# FPGA_parts.net
KiCad netlist of a schematic drawn in Altium Designer
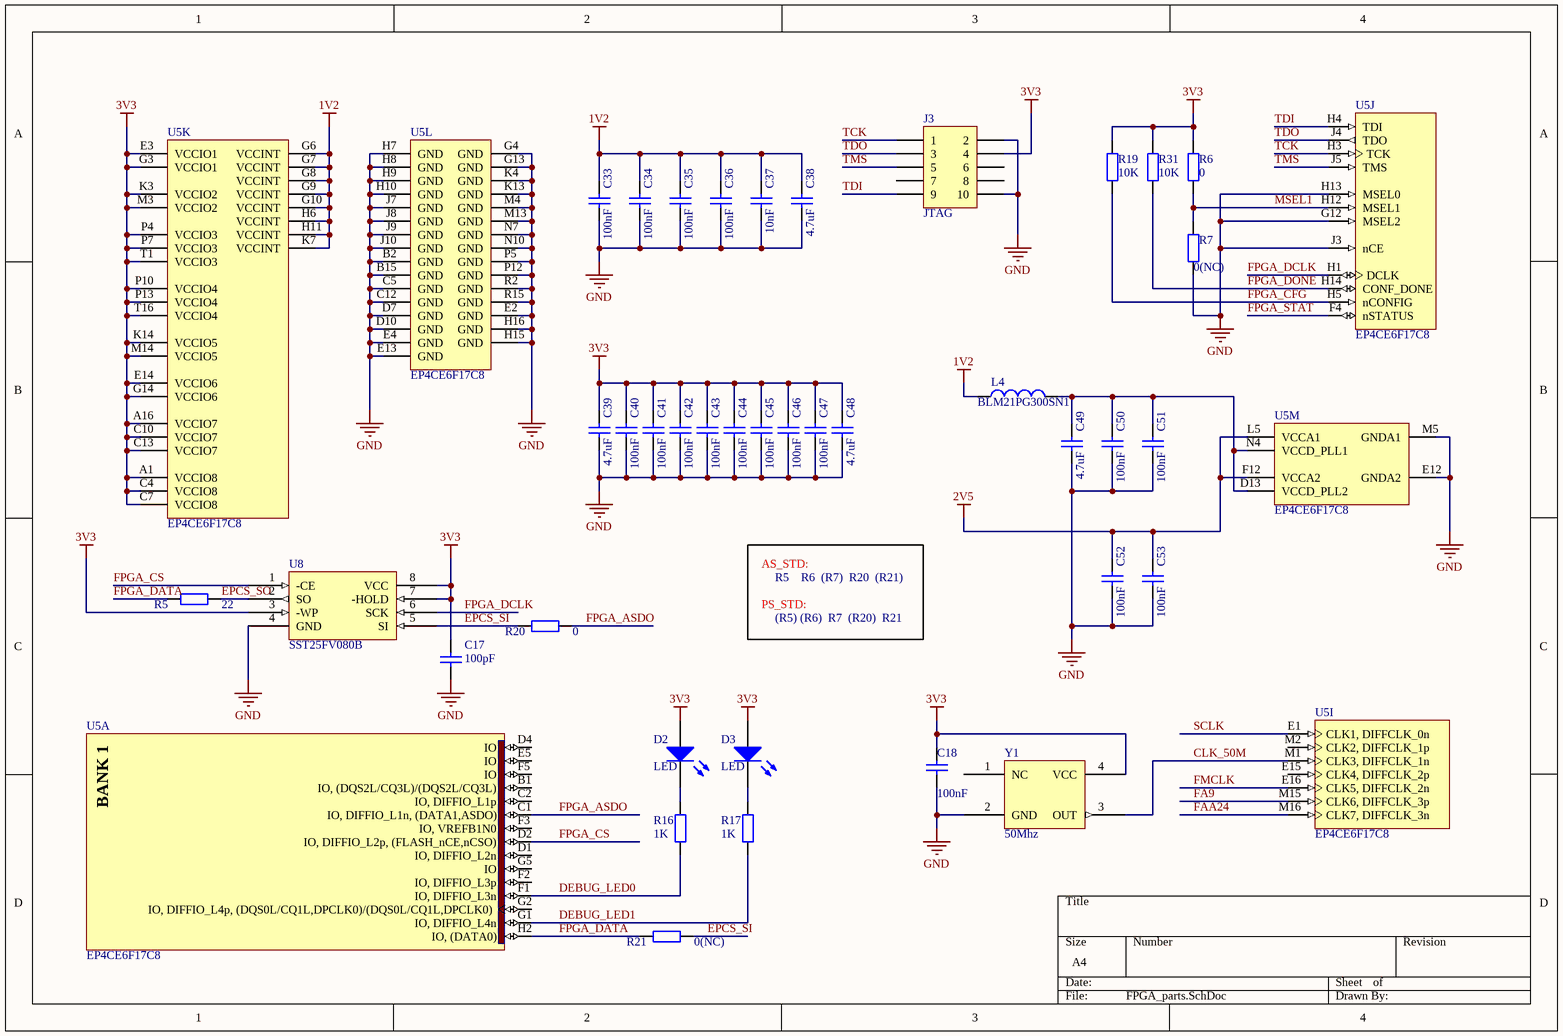
[diagram p0: FPGA_parts.SchDoc]

(export (version "E")
  (design (tool "Eeschema 10.0.6"))
  (components
    (comp (ref "C17")
      (value "100pF")
      (footprint "C0603")
      (description "Capacitor")
      (fields (field (name "PUBLISHER") "Altium Limited"))
      (libsource (lib "Miscellaneous Devices") (part "Cap"))
    )
    (comp (ref "C18")
      (value "100nF")
      (footprint "C0603")
      (description "Capacitor")
      (fields (field (name "PUBLISHER") "Altium Limited"))
      (libsource (lib "Miscellaneous Devices") (part "Cap"))
    )
    (comp (ref "C33")
      (value "100nF")
      (footprint "C0603")
      (description "Capacitor")
      (fields (field (name "PUBLISHER") "Altium Limited"))
      (libsource (lib "Miscellaneous Devices") (part "Cap"))
    )
    (comp (ref "C34")
      (value "100nF")
      (footprint "C0603")
      (description "Capacitor")
      (fields (field (name "PUBLISHER") "Altium Limited"))
      (libsource (lib "Miscellaneous Devices") (part "Cap"))
    )
    (comp (ref "C35")
      (value "100nF")
      (footprint "C0603")
      (description "Capacitor")
      (fields (field (name "PUBLISHER") "Altium Limited"))
      (libsource (lib "Miscellaneous Devices") (part "Cap"))
    )
    (comp (ref "C36")
      (value "100nF")
      (footprint "C0603")
      (description "Capacitor")
      (fields (field (name "PUBLISHER") "Altium Limited"))
      (libsource (lib "Miscellaneous Devices") (part "Cap"))
    )
    (comp (ref "C37")
      (value "10nF")
      (footprint "C0603")
      (description "Capacitor")
      (fields (field (name "PUBLISHER") "Altium Limited"))
      (libsource (lib "Miscellaneous Devices") (part "Cap"))
    )
    (comp (ref "C38")
      (value "4.7uF")
      (footprint "C0603")
      (description "Capacitor")
      (fields (field (name "PUBLISHER") "Altium Limited"))
      (libsource (lib "Miscellaneous Devices") (part "Cap"))
    )
    (comp (ref "C39")
      (value "4.7uF")
      (footprint "C0603")
      (description "Capacitor")
      (fields (field (name "PUBLISHER") "Altium Limited"))
      (libsource (lib "Miscellaneous Devices") (part "Cap"))
    )
    (comp (ref "C40")
      (value "100nF")
      (footprint "C0603")
      (description "Capacitor")
      (fields (field (name "PUBLISHER") "Altium Limited"))
      (libsource (lib "Miscellaneous Devices") (part "Cap"))
    )
    (comp (ref "C41")
      (value "100nF")
      (footprint "C0603")
      (description "Capacitor")
      (fields (field (name "PUBLISHER") "Altium Limited"))
      (libsource (lib "Miscellaneous Devices") (part "Cap"))
    )
    (comp (ref "C42")
      (value "100nF")
      (footprint "C0603")
      (description "Capacitor")
      (fields (field (name "PUBLISHER") "Altium Limited"))
      (libsource (lib "Miscellaneous Devices") (part "Cap"))
    )
    (comp (ref "C43")
      (value "100nF")
      (footprint "C0603")
      (description "Capacitor")
      (fields (field (name "PUBLISHER") "Altium Limited"))
      (libsource (lib "Miscellaneous Devices") (part "Cap"))
    )
    (comp (ref "C44")
      (value "100nF")
      (footprint "C0603")
      (description "Capacitor")
      (fields (field (name "PUBLISHER") "Altium Limited"))
      (libsource (lib "Miscellaneous Devices") (part "Cap"))
    )
    (comp (ref "C45")
      (value "100nF")
      (footprint "C0603")
      (description "Capacitor")
      (fields (field (name "PUBLISHER") "Altium Limited"))
      (libsource (lib "Miscellaneous Devices") (part "Cap"))
    )
    (comp (ref "C46")
      (value "100nF")
      (footprint "C0603")
      (description "Capacitor")
      (fields (field (name "PUBLISHER") "Altium Limited"))
      (libsource (lib "Miscellaneous Devices") (part "Cap"))
    )
    (comp (ref "C47")
      (value "100nF")
      (footprint "C0603")
      (description "Capacitor")
      (fields (field (name "PUBLISHER") "Altium Limited"))
      (libsource (lib "Miscellaneous Devices") (part "Cap"))
    )
    (comp (ref "C48")
      (value "4.7uF")
      (footprint "C0603")
      (description "Capacitor")
      (fields (field (name "PUBLISHER") "Altium Limited"))
      (libsource (lib "Miscellaneous Devices") (part "Cap"))
    )
    (comp (ref "C49")
      (value "4.7uF")
      (footprint "C0603")
      (description "Capacitor")
      (fields (field (name "PUBLISHER") "Altium Limited"))
      (libsource (lib "Miscellaneous Devices") (part "Cap"))
    )
    (comp (ref "C50")
      (value "100nF")
      (footprint "C0603")
      (description "Capacitor")
      (fields (field (name "PUBLISHER") "Altium Limited"))
      (libsource (lib "Miscellaneous Devices") (part "Cap"))
    )
    (comp (ref "C51")
      (value "100nF")
      (footprint "C0603")
      (description "Capacitor")
      (fields (field (name "PUBLISHER") "Altium Limited"))
      (libsource (lib "Miscellaneous Devices") (part "Cap"))
    )
    (comp (ref "C52")
      (value "100nF")
      (footprint "C0603")
      (description "Capacitor")
      (fields (field (name "PUBLISHER") "Altium Limited"))
      (libsource (lib "Miscellaneous Devices") (part "Cap"))
    )
    (comp (ref "C53")
      (value "100nF")
      (footprint "C0603")
      (description "Capacitor")
      (fields (field (name "PUBLISHER") "Altium Limited"))
      (libsource (lib "Miscellaneous Devices") (part "Cap"))
    )
    (comp (ref "D2")
      (value "LED")
      (footprint "D0603")
      (description "Typical RED GaAs LED")
      (fields (field (name "PUBLISHER") "Altium Limited"))
      (libsource (lib "PCB_Project1") (part "LED1"))
    )
    (comp (ref "D3")
      (value "LED")
      (footprint "D0603")
      (description "Typical RED GaAs LED")
      (fields (field (name "PUBLISHER") "Altium Limited"))
      (libsource (lib "PCB_Project1") (part "LED1"))
    )
    (comp (ref "J3")
      (value "JTAG")
      (footprint "HDR2X5")
      (description "Header, 5-Pin, Dual row")
      (fields (field (name "PUBLISHER") "Altium Limited"))
      (libsource (lib "Miscellaneous Connectors") (part "Header 5X2"))
    )
    (comp (ref "L4")
      (value "BLM21PG300SN1")
      (footprint "R0805")
      (description "Inductor")
      (fields (field (name "PUBLISHER") "Altium Limited"))
      (libsource (lib "Miscellaneous Devices") (part "Inductor"))
    )
    (comp (ref "R5")
      (value "22")
      (footprint "R0603")
      (description "Resistor")
      (fields (field (name "PUBLISHER") "Altium Limited"))
      (libsource (lib "") (part "Res2_1"))
    )
    (comp (ref "R6")
      (value "0")
      (footprint "R0603")
      (description "Resistor")
      (fields (field (name "PUBLISHER") "Altium Limited"))
      (libsource (lib "Miscellaneous Devices") (part "Res2"))
    )
    (comp (ref "R7")
      (value "0(NC)")
      (footprint "R0603")
      (description "Resistor")
      (fields (field (name "PUBLISHER") "Altium Limited"))
      (libsource (lib "Miscellaneous Devices") (part "Res2"))
    )
    (comp (ref "R16")
      (value "1K")
      (footprint "R0603")
      (description "Resistor")
      (fields (field (name "PUBLISHER") "Altium Limited"))
      (libsource (lib "Miscellaneous Devices") (part "Res2"))
    )
    (comp (ref "R17")
      (value "1K")
      (footprint "R0603")
      (description "Resistor")
      (fields (field (name "PUBLISHER") "Altium Limited"))
      (libsource (lib "Miscellaneous Devices") (part "Res2"))
    )
    (comp (ref "R19")
      (value "10K")
      (footprint "R0603")
      (description "Resistor")
      (fields (field (name "PUBLISHER") "Altium Limited"))
      (libsource (lib "Miscellaneous Devices") (part "Res2"))
    )
    (comp (ref "R20")
      (value "0")
      (footprint "R0603")
      (description "Resistor")
      (fields (field (name "PUBLISHER") "Altium Limited"))
      (libsource (lib "") (part "Res2_1"))
    )
    (comp (ref "R21")
      (value "0(NC)")
      (footprint "R0603")
      (description "Resistor")
      (fields (field (name "PUBLISHER") "Altium Limited"))
      (libsource (lib "") (part "Res2_1"))
    )
    (comp (ref "R31")
      (value "10K")
      (footprint "R0603")
      (description "Resistor")
      (fields (field (name "PUBLISHER") "Altium Limited"))
      (libsource (lib "Miscellaneous Devices") (part "Res2"))
    )
    (comp (ref "U5")
      (value "EP4CE6F17C8")
      (footprint "FBGA256")
      (fields (field (name "PUBLISHER") "Altium Limited"))
      (libsource (lib "Altera Cyclone IV E") (part "EP4CE6F17C8"))
    )
    (comp (ref "U8")
      (value "SST25FV080B")
      (footprint "SOIC-8")
      (libsource (lib "JL_SCH") (part "SST25FV080B"))
    )
    (comp (ref "Y1") (value "50Mhz") (footprint "OSC_5032") (libsource (lib "JL_SCH") (part "JZSMD5X7")))
  )
  (nets
    (net (code "1") (name "/CLK_50M") (class "Default")
      (node (ref "U5") (pin "M1") (pinfunction "CLK3,_DIFFCLK_1n_M1") (pintype "input"))
      (node (ref "Y1") (pin "3") (pinfunction "OUT_3") (pintype "output"))
    )
    (net (code "2") (name "/DEBUG_LED0") (class "Default")
      (node (ref "R16") (pin "1") (pinfunction "1_1") (pintype "passive"))
      (node (ref "U5") (pin "F1") (pinfunction "IO,_DIFFIO_L3n_F1") (pintype "bidirectional"))
    )
    (net (code "3") (name "/DEBUG_LED1") (class "Default")
      (node (ref "R17") (pin "1") (pinfunction "1_1") (pintype "passive"))
      (node (ref "U5") (pin "G1") (pinfunction "IO,_DIFFIO_L4n_G1") (pintype "bidirectional"))
    )
    (net (code "4") (name "/EPCS_SI") (class "Default")
      (node (ref "R20") (pin "1") (pinfunction "1_1") (pintype "passive"))
      (node (ref "R21") (pin "2") (pinfunction "2_2") (pintype "passive"))
      (node (ref "U8") (pin "5") (pinfunction "SI_5") (pintype "input"))
    )
    (net (code "5") (name "/EPCS_SO") (class "Default")
      (node (ref "R5") (pin "2") (pinfunction "2_2") (pintype "passive"))
      (node (ref "U8") (pin "2") (pinfunction "SO_2") (pintype "output"))
    )
    (net (code "6") (name "/FA9") (class "Default")
      (node (ref "U5") (pin "M15") (pinfunction "CLK6,_DIFFCLK_3p_M15") (pintype "input"))
    )
    (net (code "7") (name "/FAA24") (class "Default")
      (node (ref "U5") (pin "M16") (pinfunction "CLK7,_DIFFCLK_3n_M16") (pintype "input"))
    )
    (net (code "8") (name "/FMCLK") (class "Default")
      (node (ref "U5") (pin "E16") (pinfunction "CLK5,_DIFFCLK_2n_E16") (pintype "input"))
    )
    (net (code "9") (name "/FPGA_ASDO") (class "Default")
      (node (ref "R20") (pin "2") (pinfunction "2_2") (pintype "passive"))
      (node (ref "U5") (pin "C1") (pinfunction "IO,_DIFFIO_L1n,_(DATA1,ASDO)_C1") (pintype "bidirectional"))
    )
    (net (code "10") (name "/FPGA_CFG") (class "Default")
      (node (ref "R19") (pin "1") (pinfunction "1_1") (pintype "passive"))
      (node (ref "U5") (pin "H5") (pinfunction "nCONFIG_H5") (pintype "input"))
    )
    (net (code "11") (name "/FPGA_CS") (class "Default")
      (node (ref "U5") (pin "D2") (pinfunction "IO,_DIFFIO_L2p,_(FLASH_nCE,nCSO)_D2") (pintype "bidirectional"))
      (node (ref "U8") (pin "1") (pinfunction "-CE_1") (pintype "input"))
    )
    (net (code "12") (name "/FPGA_DATA") (class "Default")
      (node (ref "R21") (pin "1") (pinfunction "1_1") (pintype "passive"))
      (node (ref "R5") (pin "1") (pinfunction "1_1") (pintype "passive"))
      (node (ref "U5") (pin "H2") (pinfunction "IO,_(DATA0)_H2") (pintype "bidirectional"))
    )
    (net (code "13") (name "/FPGA_DCLK") (class "Default")
      (node (ref "U5") (pin "H1") (pinfunction "DCLK_H1") (pintype "bidirectional"))
      (node (ref "U8") (pin "6") (pinfunction "SCK_6") (pintype "input"))
    )
    (net (code "14") (name "/FPGA_DONE") (class "Default")
      (node (ref "R31") (pin "1") (pinfunction "1_1") (pintype "passive"))
      (node (ref "U5") (pin "H14") (pinfunction "CONF_DONE_H14") (pintype "bidirectional"))
    )
    (net (code "15") (name "/FPGA_STAT") (class "Default")
      (node (ref "U5") (pin "F4") (pinfunction "nSTATUS_F4") (pintype "bidirectional"))
    )
    (net (code "16") (name "/MSEL1") (class "Default")
      (node (ref "R6") (pin "1") (pinfunction "1_1") (pintype "passive"))
      (node (ref "R7") (pin "2") (pinfunction "2_2") (pintype "passive"))
      (node (ref "U5") (pin "H12") (pinfunction "MSEL1_H12") (pintype "input"))
    )
    (net (code "17") (name "/SCLK") (class "Default")
      (node (ref "U5") (pin "E1") (pinfunction "CLK1,_DIFFCLK_0n_E1") (pintype "input"))
    )
    (net (code "18") (name "/TCK") (class "Default")
      (node (ref "J3") (pin "1") (pinfunction "1_1") (pintype "passive"))
      (node (ref "U5") (pin "H3") (pinfunction "TCK_H3") (pintype "input"))
    )
    (net (code "19") (name "/TDI") (class "Default")
      (node (ref "J3") (pin "9") (pinfunction "9_9") (pintype "passive"))
      (node (ref "U5") (pin "H4") (pinfunction "TDI_H4") (pintype "input"))
    )
    (net (code "20") (name "/TDO") (class "Default")
      (node (ref "J3") (pin "3") (pinfunction "3_3") (pintype "passive"))
      (node (ref "U5") (pin "J4") (pinfunction "TDO_J4") (pintype "output"))
    )
    (net (code "21") (name "/TMS") (class "Default")
      (node (ref "J3") (pin "5") (pinfunction "5_5") (pintype "passive"))
      (node (ref "U5") (pin "J5") (pinfunction "TMS_J5") (pintype "input"))
    )
    (net (code "22") (name "1V2") (class "Default")
      (node (ref "C33") (pin "2") (pinfunction "2_2") (pintype "passive"))
      (node (ref "C34") (pin "2") (pinfunction "2_2") (pintype "passive"))
      (node (ref "C35") (pin "2") (pinfunction "2_2") (pintype "passive"))
      (node (ref "C36") (pin "2") (pinfunction "2_2") (pintype "passive"))
      (node (ref "C37") (pin "2") (pinfunction "2_2") (pintype "passive"))
      (node (ref "C38") (pin "2") (pinfunction "2_2") (pintype "passive"))
      (node (ref "L4") (pin "1") (pinfunction "1_1") (pintype "passive"))
      (node (ref "U5") (pin "G10") (pinfunction "VCCINT_G10") (pintype "power_in"))
      (node (ref "U5") (pin "G6") (pinfunction "VCCINT_G6") (pintype "power_in"))
      (node (ref "U5") (pin "G7") (pinfunction "VCCINT_G7") (pintype "power_in"))
      (node (ref "U5") (pin "G8") (pinfunction "VCCINT_G8") (pintype "power_in"))
      (node (ref "U5") (pin "G9") (pinfunction "VCCINT_G9") (pintype "power_in"))
      (node (ref "U5") (pin "H11") (pinfunction "VCCINT_H11") (pintype "power_in"))
      (node (ref "U5") (pin "H6") (pinfunction "VCCINT_H6") (pintype "power_in"))
      (node (ref "U5") (pin "K7") (pinfunction "VCCINT_K7") (pintype "power_in"))
    )
    (net (code "23") (name "2V5") (class "Default")
      (node (ref "C52") (pin "2") (pinfunction "2_2") (pintype "passive"))
      (node (ref "C53") (pin "2") (pinfunction "2_2") (pintype "passive"))
      (node (ref "U5") (pin "F12") (pinfunction "VCCA2_F12") (pintype "power_in"))
      (node (ref "U5") (pin "L5") (pinfunction "VCCA1_L5") (pintype "power_in"))
    )
    (net (code "24") (name "3V3") (class "Default")
      (node (ref "C17") (pin "2") (pinfunction "2_2") (pintype "passive"))
      (node (ref "C18") (pin "2") (pinfunction "2_2") (pintype "passive"))
      (node (ref "C39") (pin "2") (pinfunction "2_2") (pintype "passive"))
      (node (ref "C40") (pin "2") (pinfunction "2_2") (pintype "passive"))
      (node (ref "C41") (pin "2") (pinfunction "2_2") (pintype "passive"))
      (node (ref "C42") (pin "2") (pinfunction "2_2") (pintype "passive"))
      (node (ref "C43") (pin "2") (pinfunction "2_2") (pintype "passive"))
      (node (ref "C44") (pin "2") (pinfunction "2_2") (pintype "passive"))
      (node (ref "C45") (pin "2") (pinfunction "2_2") (pintype "passive"))
      (node (ref "C46") (pin "2") (pinfunction "2_2") (pintype "passive"))
      (node (ref "C47") (pin "2") (pinfunction "2_2") (pintype "passive"))
      (node (ref "C48") (pin "2") (pinfunction "2_2") (pintype "passive"))
      (node (ref "D2") (pin "1") (pinfunction "1_1") (pintype "passive"))
      (node (ref "D3") (pin "1") (pinfunction "1_1") (pintype "passive"))
      (node (ref "J3") (pin "4") (pinfunction "4_4") (pintype "passive"))
      (node (ref "R19") (pin "2") (pinfunction "2_2") (pintype "passive"))
      (node (ref "R31") (pin "2") (pinfunction "2_2") (pintype "passive"))
      (node (ref "R6") (pin "2") (pinfunction "2_2") (pintype "passive"))
      (node (ref "U5") (pin "A1") (pinfunction "VCCIO8_A1") (pintype "power_in"))
      (node (ref "U5") (pin "A16") (pinfunction "VCCIO7_A16") (pintype "power_in"))
      (node (ref "U5") (pin "C10") (pinfunction "VCCIO7_C10") (pintype "power_in"))
      (node (ref "U5") (pin "C13") (pinfunction "VCCIO7_C13") (pintype "power_in"))
      (node (ref "U5") (pin "C4") (pinfunction "VCCIO8_C4") (pintype "power_in"))
      (node (ref "U5") (pin "C7") (pinfunction "VCCIO8_C7") (pintype "power_in"))
      (node (ref "U5") (pin "E14") (pinfunction "VCCIO6_E14") (pintype "power_in"))
      (node (ref "U5") (pin "E3") (pinfunction "VCCIO1_E3") (pintype "power_in"))
      (node (ref "U5") (pin "G14") (pinfunction "VCCIO6_G14") (pintype "power_in"))
      (node (ref "U5") (pin "G3") (pinfunction "VCCIO1_G3") (pintype "power_in"))
      (node (ref "U5") (pin "K14") (pinfunction "VCCIO5_K14") (pintype "power_in"))
      (node (ref "U5") (pin "K3") (pinfunction "VCCIO2_K3") (pintype "power_in"))
      (node (ref "U5") (pin "M14") (pinfunction "VCCIO5_M14") (pintype "power_in"))
      (node (ref "U5") (pin "M3") (pinfunction "VCCIO2_M3") (pintype "power_in"))
      (node (ref "U5") (pin "P10") (pinfunction "VCCIO4_P10") (pintype "power_in"))
      (node (ref "U5") (pin "P13") (pinfunction "VCCIO4_P13") (pintype "power_in"))
      (node (ref "U5") (pin "P4") (pinfunction "VCCIO3_P4") (pintype "power_in"))
      (node (ref "U5") (pin "P7") (pinfunction "VCCIO3_P7") (pintype "power_in"))
      (node (ref "U5") (pin "T1") (pinfunction "VCCIO3_T1") (pintype "power_in"))
      (node (ref "U5") (pin "T16") (pinfunction "VCCIO4_T16") (pintype "power_in"))
      (node (ref "U8") (pin "3") (pinfunction "-WP_3") (pintype "input"))
      (node (ref "U8") (pin "7") (pinfunction "-HOLD_7") (pintype "input"))
      (node (ref "U8") (pin "8") (pinfunction "VCC_8") (pintype "power_in"))
      (node (ref "Y1") (pin "4") (pinfunction "VCC_4") (pintype "power_in"))
    )
    (net (code "25") (name "GND") (class "Default")
      (node (ref "C17") (pin "1") (pinfunction "1_1") (pintype "passive"))
      (node (ref "C18") (pin "1") (pinfunction "1_1") (pintype "passive"))
      (node (ref "C33") (pin "1") (pinfunction "1_1") (pintype "passive"))
      (node (ref "C34") (pin "1") (pinfunction "1_1") (pintype "passive"))
      (node (ref "C35") (pin "1") (pinfunction "1_1") (pintype "passive"))
      (node (ref "C36") (pin "1") (pinfunction "1_1") (pintype "passive"))
      (node (ref "C37") (pin "1") (pinfunction "1_1") (pintype "passive"))
      (node (ref "C38") (pin "1") (pinfunction "1_1") (pintype "passive"))
      (node (ref "C39") (pin "1") (pinfunction "1_1") (pintype "passive"))
      (node (ref "C40") (pin "1") (pinfunction "1_1") (pintype "passive"))
      (node (ref "C41") (pin "1") (pinfunction "1_1") (pintype "passive"))
      (node (ref "C42") (pin "1") (pinfunction "1_1") (pintype "passive"))
      (node (ref "C43") (pin "1") (pinfunction "1_1") (pintype "passive"))
      (node (ref "C44") (pin "1") (pinfunction "1_1") (pintype "passive"))
      (node (ref "C45") (pin "1") (pinfunction "1_1") (pintype "passive"))
      (node (ref "C46") (pin "1") (pinfunction "1_1") (pintype "passive"))
      (node (ref "C47") (pin "1") (pinfunction "1_1") (pintype "passive"))
      (node (ref "C48") (pin "1") (pinfunction "1_1") (pintype "passive"))
      (node (ref "C49") (pin "1") (pinfunction "1_1") (pintype "passive"))
      (node (ref "C50") (pin "1") (pinfunction "1_1") (pintype "passive"))
      (node (ref "C51") (pin "1") (pinfunction "1_1") (pintype "passive"))
      (node (ref "C52") (pin "1") (pinfunction "1_1") (pintype "passive"))
      (node (ref "C53") (pin "1") (pinfunction "1_1") (pintype "passive"))
      (node (ref "J3") (pin "10") (pinfunction "10_10") (pintype "passive"))
      (node (ref "J3") (pin "2") (pinfunction "2_2") (pintype "passive"))
      (node (ref "R7") (pin "1") (pinfunction "1_1") (pintype "passive"))
      (node (ref "U5") (pin "B15") (pinfunction "GND_B15") (pintype "power_in"))
      (node (ref "U5") (pin "B2") (pinfunction "GND_B2") (pintype "power_in"))
      (node (ref "U5") (pin "C12") (pinfunction "GND_C12") (pintype "power_in"))
      (node (ref "U5") (pin "C5") (pinfunction "GND_C5") (pintype "power_in"))
      (node (ref "U5") (pin "D10") (pinfunction "GND_D10") (pintype "power_in"))
      (node (ref "U5") (pin "D7") (pinfunction "GND_D7") (pintype "power_in"))
      (node (ref "U5") (pin "E12") (pinfunction "GNDA2_E12") (pintype "power_in"))
      (node (ref "U5") (pin "E13") (pinfunction "GND_E13") (pintype "power_in"))
      (node (ref "U5") (pin "E2") (pinfunction "GND_E2") (pintype "power_in"))
      (node (ref "U5") (pin "E4") (pinfunction "GND_E4") (pintype "power_in"))
      (node (ref "U5") (pin "G12") (pinfunction "MSEL2_G12") (pintype "input"))
      (node (ref "U5") (pin "G13") (pinfunction "GND_G13") (pintype "power_in"))
      (node (ref "U5") (pin "G4") (pinfunction "GND_G4") (pintype "power_in"))
      (node (ref "U5") (pin "H10") (pinfunction "GND_H10") (pintype "power_in"))
      (node (ref "U5") (pin "H13") (pinfunction "MSEL0_H13") (pintype "input"))
      (node (ref "U5") (pin "H15") (pinfunction "GND_H15") (pintype "power_in"))
      (node (ref "U5") (pin "H16") (pinfunction "GND_H16") (pintype "power_in"))
      (node (ref "U5") (pin "H7") (pinfunction "GND_H7") (pintype "power_in"))
      (node (ref "U5") (pin "H8") (pinfunction "GND_H8") (pintype "power_in"))
      (node (ref "U5") (pin "H9") (pinfunction "GND_H9") (pintype "power_in"))
      (node (ref "U5") (pin "J10") (pinfunction "GND_J10") (pintype "power_in"))
      (node (ref "U5") (pin "J3") (pinfunction "nCE_J3") (pintype "input"))
      (node (ref "U5") (pin "J7") (pinfunction "GND_J7") (pintype "power_in"))
      (node (ref "U5") (pin "J8") (pinfunction "GND_J8") (pintype "power_in"))
      (node (ref "U5") (pin "J9") (pinfunction "GND_J9") (pintype "power_in"))
      (node (ref "U5") (pin "K13") (pinfunction "GND_K13") (pintype "power_in"))
      (node (ref "U5") (pin "K4") (pinfunction "GND_K4") (pintype "power_in"))
      (node (ref "U5") (pin "M13") (pinfunction "GND_M13") (pintype "power_in"))
      (node (ref "U5") (pin "M4") (pinfunction "GND_M4") (pintype "power_in"))
      (node (ref "U5") (pin "M5") (pinfunction "GNDA1_M5") (pintype "power_in"))
      (node (ref "U5") (pin "N10") (pinfunction "GND_N10") (pintype "power_in"))
      (node (ref "U5") (pin "N7") (pinfunction "GND_N7") (pintype "power_in"))
      (node (ref "U5") (pin "P12") (pinfunction "GND_P12") (pintype "power_in"))
      (node (ref "U5") (pin "P5") (pinfunction "GND_P5") (pintype "power_in"))
      (node (ref "U5") (pin "R15") (pinfunction "GND_R15") (pintype "power_in"))
      (node (ref "U5") (pin "R2") (pinfunction "GND_R2") (pintype "power_in"))
      (node (ref "U8") (pin "4") (pinfunction "GND_4") (pintype "power_in"))
      (node (ref "Y1") (pin "2") (pinfunction "GND_2") (pintype "power_in"))
    )
    (net (code "26") (name "Net-(D2-Pad2)") (class "Default")
      (node (ref "D2") (pin "2") (pinfunction "2_2") (pintype "passive"))
      (node (ref "R16") (pin "2") (pinfunction "2_2") (pintype "passive"))
    )
    (net (code "27") (name "Net-(D3-Pad2)") (class "Default")
      (node (ref "D3") (pin "2") (pinfunction "2_2") (pintype "passive"))
      (node (ref "R17") (pin "2") (pinfunction "2_2") (pintype "passive"))
    )
    (net (code "28") (name "Net-(U5M-VCCD_PLL1)") (class "Default")
      (node (ref "C49") (pin "2") (pinfunction "2_2") (pintype "passive"))
      (node (ref "C50") (pin "2") (pinfunction "2_2") (pintype "passive"))
      (node (ref "C51") (pin "2") (pinfunction "2_2") (pintype "passive"))
      (node (ref "L4") (pin "2") (pinfunction "2_2") (pintype "passive"))
      (node (ref "U5") (pin "D13") (pinfunction "VCCD_PLL2_D13") (pintype "power_in"))
      (node (ref "U5") (pin "N4") (pinfunction "VCCD_PLL1_N4") (pintype "power_in"))
    )
    (net (code "29") (name "unconnected-(J3-Pad6)") (class "Default")
      (node (ref "J3") (pin "6") (pinfunction "6_6") (pintype "passive"))
    )
    (net (code "30") (name "unconnected-(J3-Pad7)") (class "Default")
      (node (ref "J3") (pin "7") (pinfunction "7_7") (pintype "passive"))
    )
    (net (code "31") (name "unconnected-(J3-Pad8)") (class "Default")
      (node (ref "J3") (pin "8") (pinfunction "8_8") (pintype "passive"))
    )
    (net (code "32") (name "unconnected-(U5A-IO,_(DQS2L{slash}CQ3L){slash}(DQS2L{slash}CQ3L)-PadB1)") (class "Default")
      (node (ref "U5") (pin "B1") (pinfunction "IO,_(DQS2L/CQ3L)/(DQS2L/CQ3L)_B1") (pintype "bidirectional"))
    )
    (net (code "33") (name "unconnected-(U5A-IO,_DIFFIO_L1p-PadC2)") (class "Default")
      (node (ref "U5") (pin "C2") (pinfunction "IO,_DIFFIO_L1p_C2") (pintype "bidirectional"))
    )
    (net (code "34") (name "unconnected-(U5A-IO,_DIFFIO_L2n-PadD1)") (class "Default")
      (node (ref "U5") (pin "D1") (pinfunction "IO,_DIFFIO_L2n_D1") (pintype "bidirectional"))
    )
    (net (code "35") (name "unconnected-(U5A-IO,_DIFFIO_L3p-PadF2)") (class "Default")
      (node (ref "U5") (pin "F2") (pinfunction "IO,_DIFFIO_L3p_F2") (pintype "bidirectional"))
    )
    (net (code "36") (name "unconnected-(U5A-IO,_DIFFIO_L4p,_(DQS0L{slash}CQ1L,DPCLK0){slash}(DQS0L{slash}CQ1L,DPCLK0)-PadG2)") (class "Default")
      (node (ref "U5") (pin "G2") (pinfunction "IO,_DIFFIO_L4p,_(DQS0L/CQ1L,DPCLK0)/(DQS0L/CQ1L,DPCLK0)_G2") (pintype "bidirectional"))
    )
    (net (code "37") (name "unconnected-(U5A-IO,_VREFB1N0-PadF3)") (class "Default")
      (node (ref "U5") (pin "F3") (pinfunction "IO,_VREFB1N0_F3") (pintype "bidirectional"))
    )
    (net (code "38") (name "unconnected-(U5A-IO-PadD4)") (class "Default")
      (node (ref "U5") (pin "D4") (pinfunction "IO_D4") (pintype "bidirectional"))
    )
    (net (code "39") (name "unconnected-(U5A-IO-PadE5)") (class "Default")
      (node (ref "U5") (pin "E5") (pinfunction "IO_E5") (pintype "bidirectional"))
    )
    (net (code "40") (name "unconnected-(U5A-IO-PadF5)") (class "Default")
      (node (ref "U5") (pin "F5") (pinfunction "IO_F5") (pintype "bidirectional"))
    )
    (net (code "41") (name "unconnected-(U5A-IO-PadG5)") (class "Default")
      (node (ref "U5") (pin "G5") (pinfunction "IO_G5") (pintype "bidirectional"))
    )
    (net (code "42") (name "unconnected-(U5I-CLK2,_DIFFCLK_1p-PadM2)") (class "Default")
      (node (ref "U5") (pin "M2") (pinfunction "CLK2,_DIFFCLK_1p_M2") (pintype "input"))
    )
    (net (code "43") (name "unconnected-(U5I-CLK4,_DIFFCLK_2p-PadE15)") (class "Default")
      (node (ref "U5") (pin "E15") (pinfunction "CLK4,_DIFFCLK_2p_E15") (pintype "input"))
    )
    (net (code "44") (name "unconnected-(Y1-NC-Pad1)") (class "Default")
      (node (ref "Y1") (pin "1") (pinfunction "NC_1") (pintype "passive"))
    )
  )
)
